# untitled.net
KiCad netlist of a schematic drawn in EAGLE
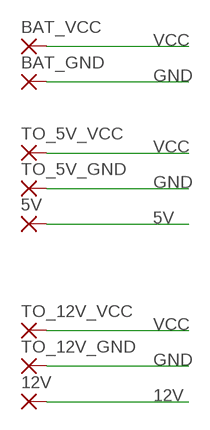
[diagram p0: schematic, sheet 1]

(export (version "E")
  (design (tool "Eeschema 10.0.6"))
  (components
    (comp (ref "5V")
      (value "3,81/1,4")
      (footprint "eagle-import:3,81_1,4")
      (libsource (lib "eagle-import") (part "3,81/1,4"))
    )
    (comp (ref "12V")
      (value "3,81/1,4")
      (footprint "eagle-import:3,81_1,4")
      (libsource (lib "eagle-import") (part "3,81/1,4"))
    )
    (comp (ref "BAT_GND")
      (value "3,81/1,4")
      (footprint "eagle-import:3,81_1,4")
      (libsource (lib "eagle-import") (part "3,81/1,4"))
    )
    (comp (ref "BAT_VCC")
      (value "3,81/1,4")
      (footprint "eagle-import:3,81_1,4")
      (libsource (lib "eagle-import") (part "3,81/1,4"))
    )
    (comp (ref "TO_5V_GND")
      (value "3,81/1,4")
      (footprint "eagle-import:3,81_1,4")
      (libsource (lib "eagle-import") (part "3,81/1,4"))
    )
    (comp (ref "TO_5V_VCC")
      (value "3,81/1,4")
      (footprint "eagle-import:3,81_1,4")
      (libsource (lib "eagle-import") (part "3,81/1,4"))
    )
    (comp (ref "TO_12V_GND")
      (value "3,81/1,4")
      (footprint "eagle-import:3,81_1,4")
      (libsource (lib "eagle-import") (part "3,81/1,4"))
    )
    (comp (ref "TO_12V_VCC")
      (value "3,81/1,4")
      (footprint "eagle-import:3,81_1,4")
      (libsource (lib "eagle-import") (part "3,81/1,4"))
    )
  )
  (nets
    (net (code "1") (name "/5V") (class "Default")
      (node (ref "5V") (pin "1") (pinfunction "P_1") (pintype "passive"))
    )
    (net (code "2") (name "/12V") (class "Default")
      (node (ref "12V") (pin "1") (pinfunction "P_1") (pintype "passive"))
    )
    (net (code "3") (name "/GND") (class "Default")
      (node (ref "BAT_GND") (pin "1") (pinfunction "P_1") (pintype "passive"))
      (node (ref "TO_12V_GND") (pin "1") (pinfunction "P_1") (pintype "passive"))
      (node (ref "TO_5V_GND") (pin "1") (pinfunction "P_1") (pintype "passive"))
    )
    (net (code "4") (name "/VCC") (class "Default")
      (node (ref "BAT_VCC") (pin "1") (pinfunction "P_1") (pintype "passive"))
      (node (ref "TO_12V_VCC") (pin "1") (pinfunction "P_1") (pintype "passive"))
      (node (ref "TO_5V_VCC") (pin "1") (pinfunction "P_1") (pintype "passive"))
    )
  )
)
